# exp3_1.net
KiCad netlist of a schematic drawn in EAGLE
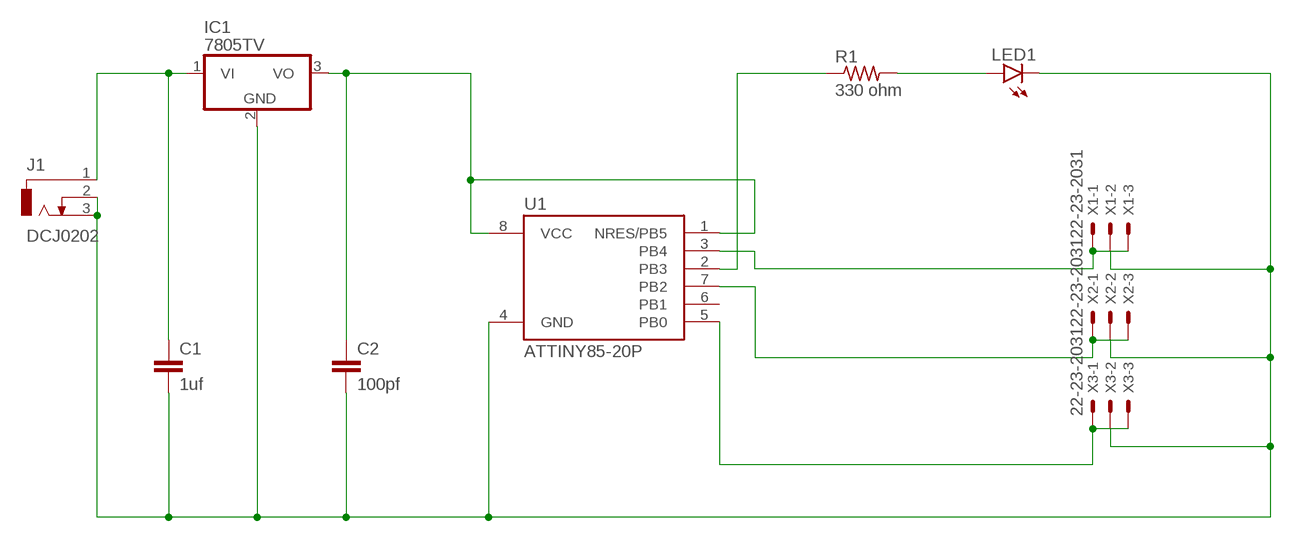
[diagram p0: schematic, sheet 1]

(export (version "E")
  (design (tool "Eeschema 10.0.6"))
  (components
    (comp (ref "C1")
      (value "1uf")
      (footprint "eagle-import:C2.5-3")
      (libsource (lib "eagle-import") (part "C2,5-3"))
    )
    (comp (ref "C2")
      (value "100pf")
      (footprint "eagle-import:C2.5-3")
      (libsource (lib "eagle-import") (part "C2,5-3"))
    )
    (comp (ref "IC1")
      (value "7805TV")
      (footprint "eagle-import:TO220V")
      (libsource (lib "eagle-import") (part "78TV05"))
    )
    (comp (ref "J1")
      (value "DCJ0202")
      (footprint "eagle-import:DCJ0202")
      (libsource (lib "eagle-import") (part "DCJ0202"))
    )
    (comp (ref "LED1")
      (value "LED3MM")
      (footprint "eagle-import:LED3MM")
      (libsource (lib "eagle-import") (part "LED3MM"))
    )
    (comp (ref "R1")
      (value "330 ohm")
      (footprint "eagle-import:0207_10")
      (libsource (lib "eagle-import") (part "R-US_0207/10"))
    )
    (comp (ref "U1")
      (value "ATTINY85-20P")
      (footprint "eagle-import:PDIP08_300MIL")
      (libsource (lib "eagle-import") (part "ATTINY85P-20"))
    )
    (comp (ref "X1")
      (value "22-23-2031")
      (footprint "eagle-import:22-23-2031")
      (fields (field (name "MF") "MOLEX"))
      (libsource (lib "eagle-import") (part "22-23-2031"))
    )
    (comp (ref "X2")
      (value "22-23-2031")
      (footprint "eagle-import:22-23-2031")
      (fields (field (name "MF") "MOLEX"))
      (libsource (lib "eagle-import") (part "22-23-2031"))
    )
    (comp (ref "X3")
      (value "22-23-2031")
      (footprint "eagle-import:22-23-2031")
      (fields (field (name "MF") "MOLEX"))
      (libsource (lib "eagle-import") (part "22-23-2031"))
    )
  )
  (nets
    (net (code "1") (name "Net-(IC1-GND)") (class "Default")
      (node (ref "C1") (pin "2") (pinfunction "2_2") (pintype "passive"))
      (node (ref "C2") (pin "2") (pinfunction "2_2") (pintype "passive"))
      (node (ref "IC1") (pin "2") (pinfunction "GND_2") (pintype "passive"))
      (node (ref "J1") (pin "2") (pinfunction "2_2") (pintype "passive"))
      (node (ref "J1") (pin "3") (pinfunction "3_3") (pintype "passive"))
      (node (ref "LED1") (pin "K") (pinfunction "C_K") (pintype "passive"))
      (node (ref "U1") (pin "4") (pinfunction "GND_4") (pintype "power_in"))
      (node (ref "X1") (pin "2") (pinfunction "S_2") (pintype "passive"))
      (node (ref "X2") (pin "2") (pinfunction "S_2") (pintype "passive"))
      (node (ref "X3") (pin "2") (pinfunction "S_2") (pintype "passive"))
    )
    (net (code "2") (name "Net-(IC1-VI)") (class "Default")
      (node (ref "C1") (pin "1") (pinfunction "1_1") (pintype "passive"))
      (node (ref "IC1") (pin "1") (pinfunction "VI_1") (pintype "input"))
      (node (ref "J1") (pin "1") (pinfunction "1_1") (pintype "passive"))
    )
    (net (code "3") (name "Net-(IC1-VO)") (class "Default")
      (node (ref "C2") (pin "1") (pinfunction "1_1") (pintype "passive"))
      (node (ref "IC1") (pin "3") (pinfunction "VO_3") (pintype "passive"))
      (node (ref "U1") (pin "1") (pinfunction "NRES/PB5_1") (pintype "bidirectional"))
      (node (ref "U1") (pin "8") (pinfunction "VCC_8") (pintype "power_in"))
    )
    (net (code "4") (name "Net-(LED1-PadA)") (class "Default")
      (node (ref "LED1") (pin "A") (pinfunction "A_A") (pintype "passive"))
      (node (ref "R1") (pin "2") (pinfunction "2_2") (pintype "passive"))
    )
    (net (code "5") (name "Net-(U1-PB0)") (class "Default")
      (node (ref "U1") (pin "5") (pinfunction "PB0_5") (pintype "bidirectional"))
      (node (ref "X3") (pin "1") (pinfunction "S_1") (pintype "passive"))
      (node (ref "X3") (pin "3") (pinfunction "S_3") (pintype "passive"))
    )
    (net (code "6") (name "Net-(U1-PB2)") (class "Default")
      (node (ref "U1") (pin "7") (pinfunction "PB2_7") (pintype "bidirectional"))
      (node (ref "X2") (pin "1") (pinfunction "S_1") (pintype "passive"))
      (node (ref "X2") (pin "3") (pinfunction "S_3") (pintype "passive"))
    )
    (net (code "7") (name "Net-(U1-PB3)") (class "Default")
      (node (ref "R1") (pin "1") (pinfunction "1_1") (pintype "passive"))
      (node (ref "U1") (pin "2") (pinfunction "PB3_2") (pintype "bidirectional"))
    )
    (net (code "8") (name "Net-(U1-PB4)") (class "Default")
      (node (ref "U1") (pin "3") (pinfunction "PB4_3") (pintype "bidirectional"))
      (node (ref "X1") (pin "1") (pinfunction "S_1") (pintype "passive"))
      (node (ref "X1") (pin "3") (pinfunction "S_3") (pintype "passive"))
    )
    (net (code "9") (name "unconnected-(U1-PB1-Pad6)") (class "Default")
      (node (ref "U1") (pin "6") (pinfunction "PB1_6") (pintype "bidirectional"))
    )
  )
)
